# AirRemoteEasyEda.net
KiCad netlist of a schematic drawn in EasyEDA
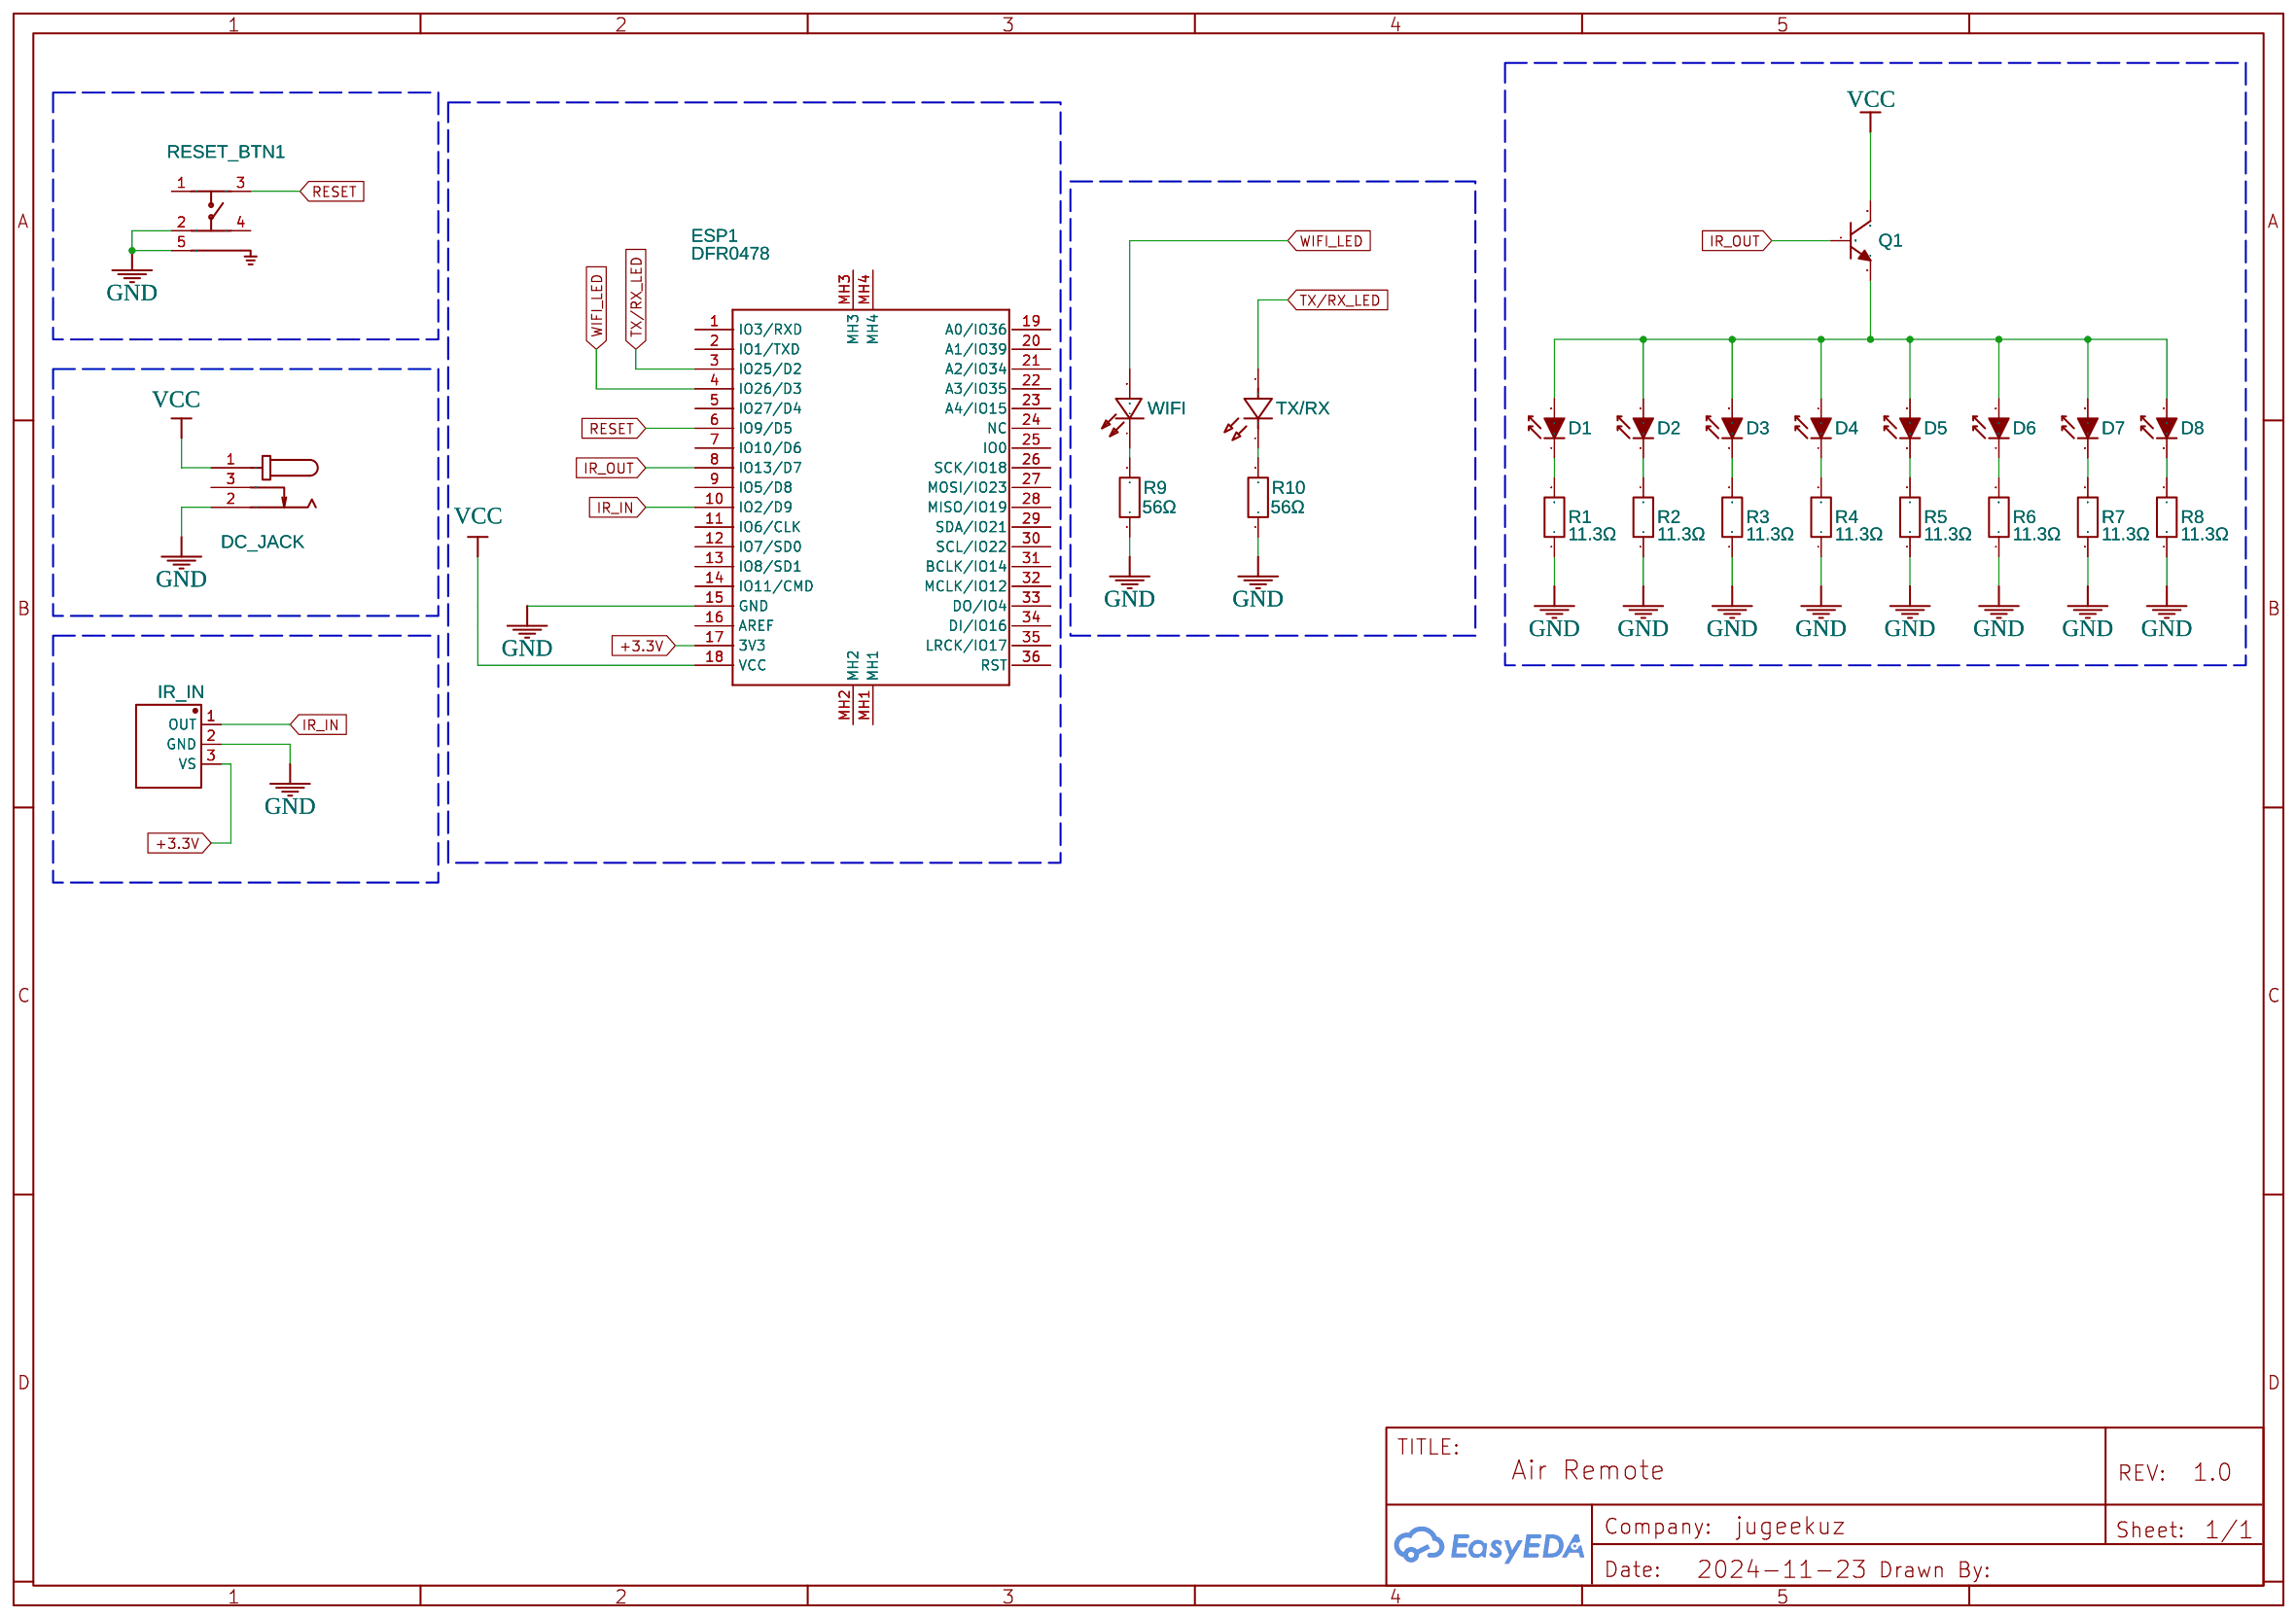
[diagram p0: schematic sheet]

(export (version "E")
  (design (tool "Eeschema 10.0.6"))
  (components
    (comp (ref "D1") (value "SFH4546") (libsource (lib "") (part "SFH4546")))
    (comp (ref "D2") (value "SFH4546") (libsource (lib "") (part "SFH4546")))
    (comp (ref "D3") (value "SFH4546") (libsource (lib "") (part "SFH4546")))
    (comp (ref "D4") (value "SFH4546") (libsource (lib "") (part "SFH4546")))
    (comp (ref "D5") (value "SFH4546") (libsource (lib "") (part "SFH4546")))
    (comp (ref "D6") (value "SFH4546") (libsource (lib "") (part "SFH4546")))
    (comp (ref "D7") (value "SFH4546") (libsource (lib "") (part "SFH4546")))
    (comp (ref "D8") (value "SFH4546") (libsource (lib "") (part "SFH4546")))
    (comp (ref "DC_JACK")
      (value "DC_JACK")
      (fields (field (name "Manufacturer Part") "KLDX-0202-BP-LT") (field (name "Manufacturer") "Kycon"))
      (libsource (lib "") (part "KLDX-0202-BP-LT"))
    )
    (comp (ref "ESP1") (value "DFR0478") (libsource (lib "") (part "DFR0478")))
    (comp (ref "LED1")
      (value "IR_IN")
      (fields (field (name "Manufacturer Part") "TSOP38238") (field (name "Manufacturer") "VISHAY(威世)"))
      (libsource (lib "") (part "TSOP38238"))
    )
    (comp (ref "Q1")
      (value "PBSS4580PA,115")
      (fields (field (name "Manufacturer") "Nexperia(安世)"))
      (libsource (lib "") (part "PBSS4580PA,115"))
    )
    (comp (ref "R1")
      (value "11.3Ω")
      (fields (field (name "Manufacturer Part") "FRC2512J130 TS") (field (name "Manufacturer") "FOJAN(富捷)"))
      (libsource (lib "") (part "FRC2512J130 TS"))
    )
    (comp (ref "R2")
      (value "11.3Ω")
      (fields (field (name "Manufacturer Part") "FRC2512J130 TS") (field (name "Manufacturer") "FOJAN(富捷)"))
      (libsource (lib "") (part "FRC2512J130 TS"))
    )
    (comp (ref "R3")
      (value "11.3Ω")
      (fields (field (name "Manufacturer Part") "FRC2512J130 TS") (field (name "Manufacturer") "FOJAN(富捷)"))
      (libsource (lib "") (part "FRC2512J130 TS"))
    )
    (comp (ref "R4")
      (value "11.3Ω")
      (fields (field (name "Manufacturer Part") "FRC2512J130 TS") (field (name "Manufacturer") "FOJAN(富捷)"))
      (libsource (lib "") (part "FRC2512J130 TS"))
    )
    (comp (ref "R5")
      (value "11.3Ω")
      (fields (field (name "Manufacturer Part") "FRC2512J130 TS") (field (name "Manufacturer") "FOJAN(富捷)"))
      (libsource (lib "") (part "FRC2512J130 TS"))
    )
    (comp (ref "R6")
      (value "11.3Ω")
      (fields (field (name "Manufacturer Part") "FRC2512J130 TS") (field (name "Manufacturer") "FOJAN(富捷)"))
      (libsource (lib "") (part "FRC2512J130 TS"))
    )
    (comp (ref "R7")
      (value "11.3Ω")
      (fields (field (name "Manufacturer Part") "FRC2512J130 TS") (field (name "Manufacturer") "FOJAN(富捷)"))
      (libsource (lib "") (part "FRC2512J130 TS"))
    )
    (comp (ref "R8")
      (value "11.3Ω")
      (fields (field (name "Manufacturer Part") "FRC2512J130 TS") (field (name "Manufacturer") "FOJAN(富捷)"))
      (libsource (lib "") (part "FRC2512J130 TS"))
    )
    (comp (ref "R9")
      (value "56Ω")
      (fields
        (field (name "Manufacturer Part") "TNPW080582R0DETA")
        (field (name "Manufacturer") "VISHAY(威世)")
      )
      (libsource (lib "") (part "TNPW080582R0DETA"))
    )
    (comp (ref "R10")
      (value "56Ω")
      (fields
        (field (name "Manufacturer Part") "TNPW080582R0DETA")
        (field (name "Manufacturer") "VISHAY(威世)")
      )
      (libsource (lib "") (part "TNPW080582R0DETA"))
    )
    (comp (ref "RESET_BTN1")
      (value "TS06-667-25-R-160-G-SMT-TR")
      (fields (field (name "Manufacturer") "CUI"))
      (libsource (lib "") (part "TS06-667-25-R-160-G-SMT-TR"))
    )
    (comp (ref "TX/RX")
      (value "TX/RX")
      (fields
        (field (name "Manufacturer Part") "HSMD-C170")
        (field (name "Manufacturer") "Broadcom/AVAGO(安华高)")
      )
      (libsource (lib "") (part "HSMD-C170"))
    )
    (comp (ref "WIFI")
      (value "WIFI")
      (fields
        (field (name "Manufacturer Part") "HSMG-C170")
        (field (name "Manufacturer") "Broadcom/AVAGO(安华高)")
      )
      (libsource (lib "") (part "HSMG-C170"))
    )
  )
  (nets
    (net (code "1") (name "+3.3V") (class "Default")
      (node (ref "ESP1") (pin "17") (pinfunction "3V3_17") (pintype "unspecified"))
      (node (ref "LED1") (pin "3") (pinfunction "VS_3") (pintype "unspecified"))
    )
    (net (code "2") (name "GND") (class "Default")
      (node (ref "DC_JACK") (pin "2") (pinfunction "2_2") (pintype "unspecified"))
      (node (ref "ESP1") (pin "15") (pinfunction "GND_15") (pintype "unspecified"))
      (node (ref "LED1") (pin "2") (pinfunction "GND_2") (pintype "unspecified"))
      (node (ref "R1") (pin "1") (pinfunction "1_1") (pintype "unspecified"))
      (node (ref "R10") (pin "1") (pinfunction "1_1") (pintype "unspecified"))
      (node (ref "R2") (pin "1") (pinfunction "1_1") (pintype "unspecified"))
      (node (ref "R3") (pin "1") (pinfunction "1_1") (pintype "unspecified"))
      (node (ref "R4") (pin "1") (pinfunction "1_1") (pintype "unspecified"))
      (node (ref "R5") (pin "1") (pinfunction "1_1") (pintype "unspecified"))
      (node (ref "R6") (pin "1") (pinfunction "1_1") (pintype "unspecified"))
      (node (ref "R7") (pin "1") (pinfunction "1_1") (pintype "unspecified"))
      (node (ref "R8") (pin "1") (pinfunction "1_1") (pintype "unspecified"))
      (node (ref "R9") (pin "1") (pinfunction "1_1") (pintype "unspecified"))
      (node (ref "RESET_BTN1") (pin "2") (pinfunction "2_2") (pintype "unspecified"))
      (node (ref "RESET_BTN1") (pin "5") (pinfunction "5_5") (pintype "unspecified"))
    )
    (net (code "3") (name "IR_IN") (class "Default")
      (node (ref "ESP1") (pin "10") (pinfunction "IO2/D9_10") (pintype "unspecified"))
      (node (ref "LED1") (pin "1") (pinfunction "OUT_1") (pintype "unspecified"))
    )
    (net (code "4") (name "IR_OUT") (class "Default")
      (node (ref "ESP1") (pin "8") (pinfunction "IO13/D7_8") (pintype "unspecified"))
      (node (ref "Q1") (pin "1") (pinfunction "B_1") (pintype "unspecified"))
    )
    (net (code "5") (name "Net-(D1-A)") (class "Default")
      (node (ref "D1") (pin "2") (pinfunction "A_2") (pintype "unspecified"))
      (node (ref "D2") (pin "2") (pinfunction "A_2") (pintype "unspecified"))
      (node (ref "D3") (pin "2") (pinfunction "A_2") (pintype "unspecified"))
      (node (ref "D4") (pin "2") (pinfunction "A_2") (pintype "unspecified"))
      (node (ref "D5") (pin "2") (pinfunction "A_2") (pintype "unspecified"))
      (node (ref "D6") (pin "2") (pinfunction "A_2") (pintype "unspecified"))
      (node (ref "D7") (pin "2") (pinfunction "A_2") (pintype "unspecified"))
      (node (ref "D8") (pin "2") (pinfunction "A_2") (pintype "unspecified"))
      (node (ref "Q1") (pin "2") (pinfunction "E_2") (pintype "unspecified"))
    )
    (net (code "6") (name "Net-(D1-K)") (class "Default")
      (node (ref "D1") (pin "1") (pinfunction "K_1") (pintype "unspecified"))
      (node (ref "R1") (pin "2") (pinfunction "2_2") (pintype "unspecified"))
    )
    (net (code "7") (name "Net-(D2-K)") (class "Default")
      (node (ref "D2") (pin "1") (pinfunction "K_1") (pintype "unspecified"))
      (node (ref "R2") (pin "2") (pinfunction "2_2") (pintype "unspecified"))
    )
    (net (code "8") (name "Net-(D3-K)") (class "Default")
      (node (ref "D3") (pin "1") (pinfunction "K_1") (pintype "unspecified"))
      (node (ref "R3") (pin "2") (pinfunction "2_2") (pintype "unspecified"))
    )
    (net (code "9") (name "Net-(D4-K)") (class "Default")
      (node (ref "D4") (pin "1") (pinfunction "K_1") (pintype "unspecified"))
      (node (ref "R4") (pin "2") (pinfunction "2_2") (pintype "unspecified"))
    )
    (net (code "10") (name "Net-(D5-K)") (class "Default")
      (node (ref "D5") (pin "1") (pinfunction "K_1") (pintype "unspecified"))
      (node (ref "R5") (pin "2") (pinfunction "2_2") (pintype "unspecified"))
    )
    (net (code "11") (name "Net-(D6-K)") (class "Default")
      (node (ref "D6") (pin "1") (pinfunction "K_1") (pintype "unspecified"))
      (node (ref "R6") (pin "2") (pinfunction "2_2") (pintype "unspecified"))
    )
    (net (code "12") (name "Net-(D7-K)") (class "Default")
      (node (ref "D7") (pin "1") (pinfunction "K_1") (pintype "unspecified"))
      (node (ref "R7") (pin "2") (pinfunction "2_2") (pintype "unspecified"))
    )
    (net (code "13") (name "Net-(D8-K)") (class "Default")
      (node (ref "D8") (pin "1") (pinfunction "K_1") (pintype "unspecified"))
      (node (ref "R8") (pin "2") (pinfunction "2_2") (pintype "unspecified"))
    )
    (net (code "14") (name "Net-(R9-Pad2)") (class "Default")
      (node (ref "R9") (pin "2") (pinfunction "2_2") (pintype "unspecified"))
      (node (ref "WIFI") (pin "1") (pinfunction "1_1") (pintype "unspecified"))
    )
    (net (code "15") (name "Net-(TX/RX-K)") (class "Default")
      (node (ref "R10") (pin "2") (pinfunction "2_2") (pintype "unspecified"))
      (node (ref "TX/RX") (pin "1") (pinfunction "K_1") (pintype "unspecified"))
    )
    (net (code "16") (name "RESET") (class "Default")
      (node (ref "ESP1") (pin "6") (pinfunction "IO9/D5_6") (pintype "unspecified"))
      (node (ref "RESET_BTN1") (pin "3") (pinfunction "3_3") (pintype "unspecified"))
    )
    (net (code "17") (name "TX{slash}RX_LED") (class "Default")
      (node (ref "ESP1") (pin "3") (pinfunction "IO25/D2_3") (pintype "unspecified"))
      (node (ref "TX/RX") (pin "2") (pinfunction "A_2") (pintype "unspecified"))
    )
    (net (code "18") (name "VCC") (class "Default")
      (node (ref "DC_JACK") (pin "1") (pinfunction "1_1") (pintype "unspecified"))
      (node (ref "ESP1") (pin "18") (pinfunction "VCC_18") (pintype "unspecified"))
      (node (ref "Q1") (pin "3") (pinfunction "C_3") (pintype "unspecified"))
    )
    (net (code "19") (name "WIFI_LED") (class "Default")
      (node (ref "ESP1") (pin "4") (pinfunction "IO26/D3_4") (pintype "unspecified"))
      (node (ref "WIFI") (pin "2") (pinfunction "2_2") (pintype "unspecified"))
    )
    (net (code "20") (name "unconnected-(DC_JACK-Pad3)") (class "Default")
      (node (ref "DC_JACK") (pin "3") (pinfunction "3_3") (pintype "unspecified"))
    )
    (net (code "21") (name "unconnected-(ESP1-A0{slash}IO36-Pad19)") (class "Default")
      (node (ref "ESP1") (pin "19") (pinfunction "A0/IO36_19") (pintype "unspecified"))
    )
    (net (code "22") (name "unconnected-(ESP1-A1{slash}IO39-Pad20)") (class "Default")
      (node (ref "ESP1") (pin "20") (pinfunction "A1/IO39_20") (pintype "unspecified"))
    )
    (net (code "23") (name "unconnected-(ESP1-A2{slash}IO34-Pad21)") (class "Default")
      (node (ref "ESP1") (pin "21") (pinfunction "A2/IO34_21") (pintype "unspecified"))
    )
    (net (code "24") (name "unconnected-(ESP1-A3{slash}IO35-Pad22)") (class "Default")
      (node (ref "ESP1") (pin "22") (pinfunction "A3/IO35_22") (pintype "unspecified"))
    )
    (net (code "25") (name "unconnected-(ESP1-A4{slash}IO15-Pad23)") (class "Default")
      (node (ref "ESP1") (pin "23") (pinfunction "A4/IO15_23") (pintype "unspecified"))
    )
    (net (code "26") (name "unconnected-(ESP1-AREF-Pad16)") (class "Default")
      (node (ref "ESP1") (pin "16") (pinfunction "AREF_16") (pintype "unspecified"))
    )
    (net (code "27") (name "unconnected-(ESP1-BCLK{slash}IO14-Pad31)") (class "Default")
      (node (ref "ESP1") (pin "31") (pinfunction "BCLK/IO14_31") (pintype "unspecified"))
    )
    (net (code "28") (name "unconnected-(ESP1-DI{slash}IO16-Pad34)") (class "Default")
      (node (ref "ESP1") (pin "34") (pinfunction "DI/IO16_34") (pintype "unspecified"))
    )
    (net (code "29") (name "unconnected-(ESP1-DO{slash}IO4-Pad33)") (class "Default")
      (node (ref "ESP1") (pin "33") (pinfunction "DO/IO4_33") (pintype "unspecified"))
    )
    (net (code "30") (name "unconnected-(ESP1-IO0-Pad25)") (class "Default")
      (node (ref "ESP1") (pin "25") (pinfunction "IO0_25") (pintype "unspecified"))
    )
    (net (code "31") (name "unconnected-(ESP1-IO1{slash}TXD-Pad2)") (class "Default")
      (node (ref "ESP1") (pin "2") (pinfunction "IO1/TXD_2") (pintype "unspecified"))
    )
    (net (code "32") (name "unconnected-(ESP1-IO3{slash}RXD-Pad1)") (class "Default")
      (node (ref "ESP1") (pin "1") (pinfunction "IO3/RXD_1") (pintype "unspecified"))
    )
    (net (code "33") (name "unconnected-(ESP1-IO5{slash}D8-Pad9)") (class "Default")
      (node (ref "ESP1") (pin "9") (pinfunction "IO5/D8_9") (pintype "unspecified"))
    )
    (net (code "34") (name "unconnected-(ESP1-IO6{slash}CLK-Pad11)") (class "Default")
      (node (ref "ESP1") (pin "11") (pinfunction "IO6/CLK_11") (pintype "unspecified"))
    )
    (net (code "35") (name "unconnected-(ESP1-IO7{slash}SD0-Pad12)") (class "Default")
      (node (ref "ESP1") (pin "12") (pinfunction "IO7/SD0_12") (pintype "unspecified"))
    )
    (net (code "36") (name "unconnected-(ESP1-IO8{slash}SD1-Pad13)") (class "Default")
      (node (ref "ESP1") (pin "13") (pinfunction "IO8/SD1_13") (pintype "unspecified"))
    )
    (net (code "37") (name "unconnected-(ESP1-IO10{slash}D6-Pad7)") (class "Default")
      (node (ref "ESP1") (pin "7") (pinfunction "IO10/D6_7") (pintype "unspecified"))
    )
    (net (code "38") (name "unconnected-(ESP1-IO11{slash}CMD-Pad14)") (class "Default")
      (node (ref "ESP1") (pin "14") (pinfunction "IO11/CMD_14") (pintype "unspecified"))
    )
    (net (code "39") (name "unconnected-(ESP1-IO27{slash}D4-Pad5)") (class "Default")
      (node (ref "ESP1") (pin "5") (pinfunction "IO27/D4_5") (pintype "unspecified"))
    )
    (net (code "40") (name "unconnected-(ESP1-LRCK{slash}IO17-Pad35)") (class "Default")
      (node (ref "ESP1") (pin "35") (pinfunction "LRCK/IO17_35") (pintype "unspecified"))
    )
    (net (code "41") (name "unconnected-(ESP1-MCLK{slash}IO12-Pad32)") (class "Default")
      (node (ref "ESP1") (pin "32") (pinfunction "MCLK/IO12_32") (pintype "unspecified"))
    )
    (net (code "42") (name "unconnected-(ESP1-MISO{slash}IO19-Pad28)") (class "Default")
      (node (ref "ESP1") (pin "28") (pinfunction "MISO/IO19_28") (pintype "unspecified"))
    )
    (net (code "43") (name "unconnected-(ESP1-MOSI{slash}IO23-Pad27)") (class "Default")
      (node (ref "ESP1") (pin "27") (pinfunction "MOSI/IO23_27") (pintype "unspecified"))
    )
    (net (code "44") (name "unconnected-(ESP1-NC-Pad24)") (class "Default")
      (node (ref "ESP1") (pin "24") (pinfunction "NC_24") (pintype "unspecified"))
    )
    (net (code "45") (name "unconnected-(ESP1-PadMH1)") (class "Default")
      (node (ref "ESP1") (pin "MH1") (pinfunction "MH1_MH1") (pintype "unspecified"))
    )
    (net (code "46") (name "unconnected-(ESP1-PadMH2)") (class "Default")
      (node (ref "ESP1") (pin "MH2") (pinfunction "MH2_MH2") (pintype "unspecified"))
    )
    (net (code "47") (name "unconnected-(ESP1-PadMH3)") (class "Default")
      (node (ref "ESP1") (pin "MH3") (pinfunction "MH3_MH3") (pintype "unspecified"))
    )
    (net (code "48") (name "unconnected-(ESP1-PadMH4)") (class "Default")
      (node (ref "ESP1") (pin "MH4") (pinfunction "MH4_MH4") (pintype "unspecified"))
    )
    (net (code "49") (name "unconnected-(ESP1-RST-Pad36)") (class "Default")
      (node (ref "ESP1") (pin "36") (pinfunction "RST_36") (pintype "unspecified"))
    )
    (net (code "50") (name "unconnected-(ESP1-SCK{slash}IO18-Pad26)") (class "Default")
      (node (ref "ESP1") (pin "26") (pinfunction "SCK/IO18_26") (pintype "unspecified"))
    )
    (net (code "51") (name "unconnected-(ESP1-SCL{slash}IO22-Pad30)") (class "Default")
      (node (ref "ESP1") (pin "30") (pinfunction "SCL/IO22_30") (pintype "unspecified"))
    )
    (net (code "52") (name "unconnected-(ESP1-SDA{slash}IO21-Pad29)") (class "Default")
      (node (ref "ESP1") (pin "29") (pinfunction "SDA/IO21_29") (pintype "unspecified"))
    )
    (net (code "53") (name "unconnected-(RESET_BTN1-Pad1)") (class "Default")
      (node (ref "RESET_BTN1") (pin "1") (pinfunction "1_1") (pintype "unspecified"))
    )
    (net (code "54") (name "unconnected-(RESET_BTN1-Pad4)") (class "Default")
      (node (ref "RESET_BTN1") (pin "4") (pinfunction "4_4") (pintype "unspecified"))
    )
  )
)
